# QCopterFC_LED_Sch.net
KiCad netlist of a schematic drawn in Altium Designer
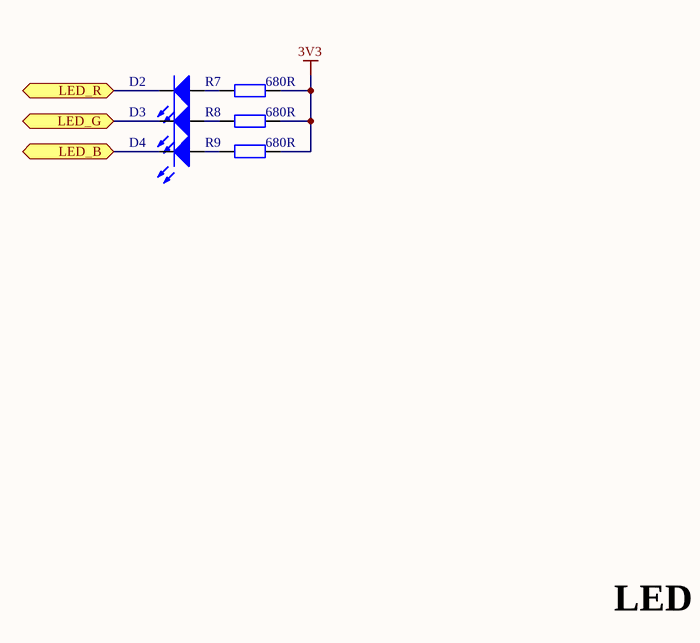
[diagram p0: QCopterFC_LED_Sch.SchDoc]

(export (version "E")
  (design (tool "Eeschema 10.0.6"))
  (components
    (comp (ref "D2")
      (value "LED_0603_RED")
      (footprint "PCB_Active:LED_0603_RED")
      (description "LED")
      (libsource (lib "SCH_Active") (part "LED_0603_RED"))
    )
    (comp (ref "D3")
      (value "LED_0603_GREEN")
      (footprint "PCB_Active:LED_0603_GREEN")
      (description "LED")
      (libsource (lib "SCH_Active") (part "LED_0603_GREEN"))
    )
    (comp (ref "D4")
      (value "LED_0603_BLUE")
      (footprint "PCB_Active:LED_0603_BLUE")
      (description "LED")
      (libsource (lib "SCH_Active") (part "LED_0603_BLUE"))
    )
    (comp (ref "R7")
      (value "680R")
      (footprint "PCB_Passive:RES_0603")
      (description "Resistor")
      (fields (field (name "Comment") "Res_0603"))
      (libsource (lib "SCH_Passive") (part "Res_0603"))
    )
    (comp (ref "R8")
      (value "680R")
      (footprint "PCB_Passive:RES_0603")
      (description "Resistor")
      (fields (field (name "Comment") "Res_0603"))
      (libsource (lib "SCH_Passive") (part "Res_0603"))
    )
    (comp (ref "R9")
      (value "680R")
      (footprint "PCB_Passive:RES_0603")
      (description "Resistor")
      (fields (field (name "Comment") "Res_0603"))
      (libsource (lib "SCH_Passive") (part "Res_0603"))
    )
  )
  (nets
    (net (code "1") (name "/LED_B") (class "Default")
      (node (ref "D4") (pin "2") (pinfunction "K_2") (pintype "passive"))
    )
    (net (code "2") (name "/LED_G") (class "Default")
      (node (ref "D3") (pin "2") (pinfunction "K_2") (pintype "passive"))
    )
    (net (code "3") (name "/LED_R") (class "Default")
      (node (ref "D2") (pin "2") (pinfunction "K_2") (pintype "passive"))
    )
    (net (code "4") (name "3V3") (class "Default")
      (node (ref "R7") (pin "2") (pinfunction "2_2") (pintype "passive"))
      (node (ref "R8") (pin "2") (pinfunction "2_2") (pintype "passive"))
      (node (ref "R9") (pin "2") (pinfunction "2_2") (pintype "passive"))
    )
    (net (code "5") (name "Net-(D2-A)") (class "Default")
      (node (ref "D2") (pin "1") (pinfunction "A_1") (pintype "passive"))
      (node (ref "R7") (pin "1") (pinfunction "1_1") (pintype "passive"))
    )
    (net (code "6") (name "Net-(D3-A)") (class "Default")
      (node (ref "D3") (pin "1") (pinfunction "A_1") (pintype "passive"))
      (node (ref "R8") (pin "1") (pinfunction "1_1") (pintype "passive"))
    )
    (net (code "7") (name "Net-(D4-A)") (class "Default")
      (node (ref "D4") (pin "1") (pinfunction "A_1") (pintype "passive"))
      (node (ref "R9") (pin "1") (pinfunction "1_1") (pintype "passive"))
    )
  )
)
